# dataLogger-TR.net
KiCad netlist of a schematic drawn in EAGLE
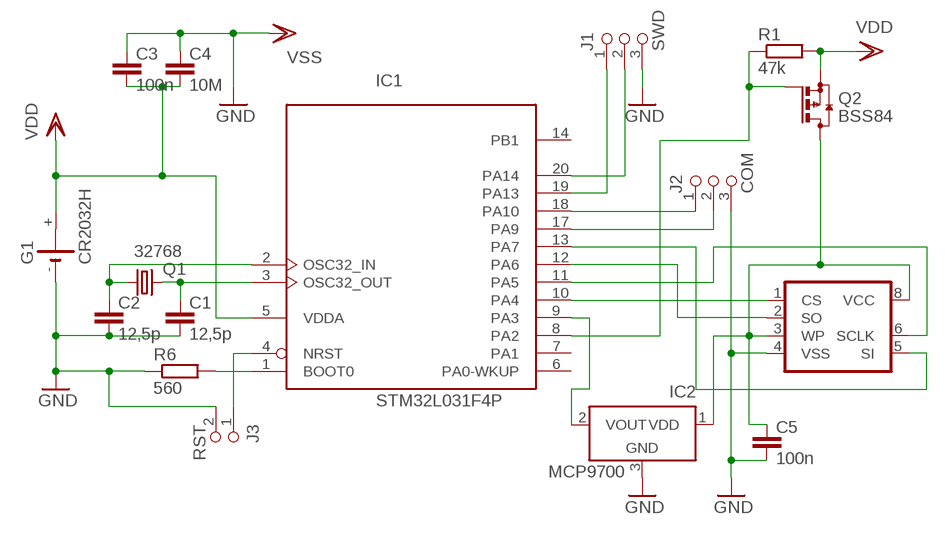
[diagram p0: schematic, sheet 1]

(export (version "E")
  (design (tool "Eeschema 10.0.6"))
  (components
    (comp (ref "C1")
      (value "12,5p")
      (footprint "eagle-import:0805")
      (libsource (lib "eagle-import") (part "C0805"))
    )
    (comp (ref "C2")
      (value "12,5p")
      (footprint "eagle-import:0805")
      (libsource (lib "eagle-import") (part "C0805"))
    )
    (comp (ref "C3")
      (value "100n")
      (footprint "eagle-import:0805")
      (libsource (lib "eagle-import") (part "C0805"))
    )
    (comp (ref "C4")
      (value "10M")
      (footprint "eagle-import:0805")
      (libsource (lib "eagle-import") (part "C0805"))
    )
    (comp (ref "C5")
      (value "100n")
      (footprint "eagle-import:0805")
      (libsource (lib "eagle-import") (part "C0805"))
    )
    (comp (ref "G1")
      (value "CR2032H")
      (footprint "eagle-import:CR2032H")
      (libsource (lib "eagle-import") (part "CR2032H"))
    )
    (comp (ref "IC1")
      (value "STM32L031F4P")
      (footprint "eagle-import:TSSOP20-I")
      (libsource (lib "eagle-import") (part "STM32L031FP4"))
    )
    (comp (ref "IC2")
      (value "MCP9700")
      (footprint "eagle-import:SOT23")
      (libsource (lib "eagle-import") (part "MCP9700"))
    )
    (comp (ref "J1")
      (value "SWD")
      (footprint "eagle-import:HEAD1X3I")
      (libsource (lib "eagle-import") (part "CON1X3HEAD1X3I"))
    )
    (comp (ref "J2")
      (value "COM")
      (footprint "eagle-import:HEAD1X3I")
      (libsource (lib "eagle-import") (part "CON1X3HEAD1X3I"))
    )
    (comp (ref "J3")
      (value "RST")
      (footprint "eagle-import:HEAD1X2I")
      (libsource (lib "eagle-import") (part "CON1X2HEAD1X2I"))
    )
    (comp (ref "Q1")
      (value "32768")
      (footprint "eagle-import:TC38H-SMD")
      (libsource (lib "eagle-import") (part "CRYSTALTC38H-SMD"))
    )
    (comp (ref "Q2")
      (value "BSS84")
      (footprint "eagle-import:SOT23")
      (libsource (lib "eagle-import") (part "BSS84"))
    )
    (comp (ref "R1")
      (value "47k")
      (footprint "eagle-import:R0805")
      (libsource (lib "eagle-import") (part "R-EU_R0805"))
    )
    (comp (ref "R6")
      (value "560")
      (footprint "eagle-import:R0805")
      (libsource (lib "eagle-import") (part "R-EU_R0805"))
    )
    (comp (ref "U$1")
      (value "GD25")
      (footprint "eagle-import:SO08")
      (libsource (lib "eagle-import") (part "GD25SO08"))
    )
  )
  (nets
    (net (code "1") (name "GND") (class "Default")
      (node (ref "C1") (pin "2") (pinfunction "2_2") (pintype "passive"))
      (node (ref "C2") (pin "2") (pinfunction "2_2") (pintype "passive"))
      (node (ref "C3") (pin "1") (pinfunction "1_1") (pintype "passive"))
      (node (ref "C4") (pin "1") (pinfunction "1_1") (pintype "passive"))
      (node (ref "C5") (pin "2") (pinfunction "2_2") (pintype "passive"))
      (node (ref "G1") (pin "-") (pinfunction "-_-") (pintype "passive"))
      (node (ref "IC2") (pin "3") (pinfunction "GND_3") (pintype "power_in"))
      (node (ref "J1") (pin "3") (pinfunction "3_3") (pintype "passive"))
      (node (ref "J2") (pin "3") (pinfunction "3_3") (pintype "passive"))
      (node (ref "J3") (pin "2") (pinfunction "2_2") (pintype "passive"))
      (node (ref "R6") (pin "1") (pinfunction "1_1") (pintype "passive"))
      (node (ref "U$1") (pin "4") (pinfunction "VSS_4") (pintype "power_in"))
    )
    (net (code "2") (name "Net-(IC1A-BOOT0)") (class "Default")
      (node (ref "IC1") (pin "1") (pinfunction "BOOT0_1") (pintype "input"))
      (node (ref "R6") (pin "2") (pinfunction "2_2") (pintype "passive"))
    )
    (net (code "3") (name "Net-(IC1A-NRST)") (class "Default")
      (node (ref "IC1") (pin "4") (pinfunction "NRST_4") (pintype "bidirectional"))
      (node (ref "J3") (pin "1") (pinfunction "1_1") (pintype "passive"))
    )
    (net (code "4") (name "Net-(IC1A-OSC32_IN)") (class "Default")
      (node (ref "C2") (pin "1") (pinfunction "1_1") (pintype "passive"))
      (node (ref "IC1") (pin "2") (pinfunction "OSC32_IN_2") (pintype "bidirectional"))
      (node (ref "Q1") (pin "P$1") (pinfunction "1_P$1") (pintype "passive"))
    )
    (net (code "5") (name "Net-(IC1A-OSC32_OUT)") (class "Default")
      (node (ref "C1") (pin "1") (pinfunction "1_1") (pintype "passive"))
      (node (ref "IC1") (pin "3") (pinfunction "OSC32_OUT_3") (pintype "bidirectional"))
      (node (ref "Q1") (pin "P$2") (pinfunction "2_P$2") (pintype "passive"))
    )
    (net (code "6") (name "Net-(IC1A-PA2)") (class "Default")
      (node (ref "IC1") (pin "8") (pinfunction "PA2_8") (pintype "bidirectional"))
      (node (ref "Q2") (pin "1") (pinfunction "G_1") (pintype "passive"))
      (node (ref "R1") (pin "1") (pinfunction "1_1") (pintype "passive"))
    )
    (net (code "7") (name "Net-(IC1A-PA3)") (class "Default")
      (node (ref "IC1") (pin "9") (pinfunction "PA3_9") (pintype "bidirectional"))
      (node (ref "IC2") (pin "2") (pinfunction "VOUT_2") (pintype "input"))
    )
    (net (code "8") (name "Net-(IC1A-PA4)") (class "Default")
      (node (ref "IC1") (pin "10") (pinfunction "PA4_10") (pintype "bidirectional"))
      (node (ref "U$1") (pin "1") (pinfunction "CS_1") (pintype "bidirectional"))
    )
    (net (code "9") (name "Net-(IC1A-PA5)") (class "Default")
      (node (ref "IC1") (pin "11") (pinfunction "PA5_11") (pintype "bidirectional"))
      (node (ref "U$1") (pin "6") (pinfunction "SCLK_6") (pintype "bidirectional"))
    )
    (net (code "10") (name "Net-(IC1A-PA6)") (class "Default")
      (node (ref "IC1") (pin "12") (pinfunction "PA6_12") (pintype "bidirectional"))
      (node (ref "U$1") (pin "2") (pinfunction "SO_2") (pintype "bidirectional"))
    )
    (net (code "11") (name "Net-(IC1A-PA7)") (class "Default")
      (node (ref "IC1") (pin "13") (pinfunction "PA7_13") (pintype "bidirectional"))
      (node (ref "U$1") (pin "5") (pinfunction "SI_5") (pintype "bidirectional"))
    )
    (net (code "12") (name "Net-(IC1A-PA9)") (class "Default")
      (node (ref "IC1") (pin "17") (pinfunction "PA9_17") (pintype "bidirectional"))
      (node (ref "J2") (pin "2") (pinfunction "2_2") (pintype "passive"))
    )
    (net (code "13") (name "Net-(IC1A-PA10)") (class "Default")
      (node (ref "IC1") (pin "18") (pinfunction "PA10_18") (pintype "bidirectional"))
      (node (ref "J2") (pin "1") (pinfunction "1_1") (pintype "passive"))
    )
    (net (code "14") (name "Net-(IC1A-PA13)") (class "Default")
      (node (ref "IC1") (pin "19") (pinfunction "PA13_19") (pintype "bidirectional"))
      (node (ref "J1") (pin "1") (pinfunction "1_1") (pintype "passive"))
    )
    (net (code "15") (name "Net-(IC1A-PA14)") (class "Default")
      (node (ref "IC1") (pin "20") (pinfunction "PA14_20") (pintype "bidirectional"))
      (node (ref "J1") (pin "2") (pinfunction "2_2") (pintype "passive"))
    )
    (net (code "16") (name "Net-(IC2-VDD)") (class "Default")
      (node (ref "C5") (pin "1") (pinfunction "1_1") (pintype "passive"))
      (node (ref "IC2") (pin "1") (pinfunction "VDD_1") (pintype "input"))
      (node (ref "Q2") (pin "3") (pinfunction "D_3") (pintype "passive"))
      (node (ref "U$1") (pin "3") (pinfunction "WP_3") (pintype "bidirectional"))
      (node (ref "U$1") (pin "8") (pinfunction "VCC_8") (pintype "power_in"))
    )
    (net (code "17") (name "VDD") (class "Default")
      (node (ref "C3") (pin "2") (pinfunction "2_2") (pintype "passive"))
      (node (ref "C4") (pin "2") (pinfunction "2_2") (pintype "passive"))
      (node (ref "G1") (pin "+") (pinfunction "+_+") (pintype "passive"))
      (node (ref "IC1") (pin "5") (pinfunction "VDDA_5") (pintype "power_in"))
      (node (ref "Q2") (pin "2") (pinfunction "S_2") (pintype "passive"))
      (node (ref "R1") (pin "2") (pinfunction "2_2") (pintype "passive"))
    )
    (net (code "18") (name "unconnected-(G1-+-Pad+@1)") (class "Default")
      (node (ref "G1") (pin "+@1") (pinfunction "+_+@1") (pintype "passive"))
    )
    (net (code "19") (name "unconnected-(IC1A-PA0-WKUP-Pad6)") (class "Default")
      (node (ref "IC1") (pin "6") (pinfunction "PA0-WKUP_6") (pintype "bidirectional"))
    )
    (net (code "20") (name "unconnected-(IC1A-PA1-Pad7)") (class "Default")
      (node (ref "IC1") (pin "7") (pinfunction "PA1_7") (pintype "bidirectional"))
    )
    (net (code "21") (name "unconnected-(IC1A-PB1-Pad14)") (class "Default")
      (node (ref "IC1") (pin "14") (pinfunction "PB1_14") (pintype "bidirectional"))
    )
  )
)
